# 01-MYB-Y6ULX.net
KiCad netlist of a schematic drawn in Altium Designer
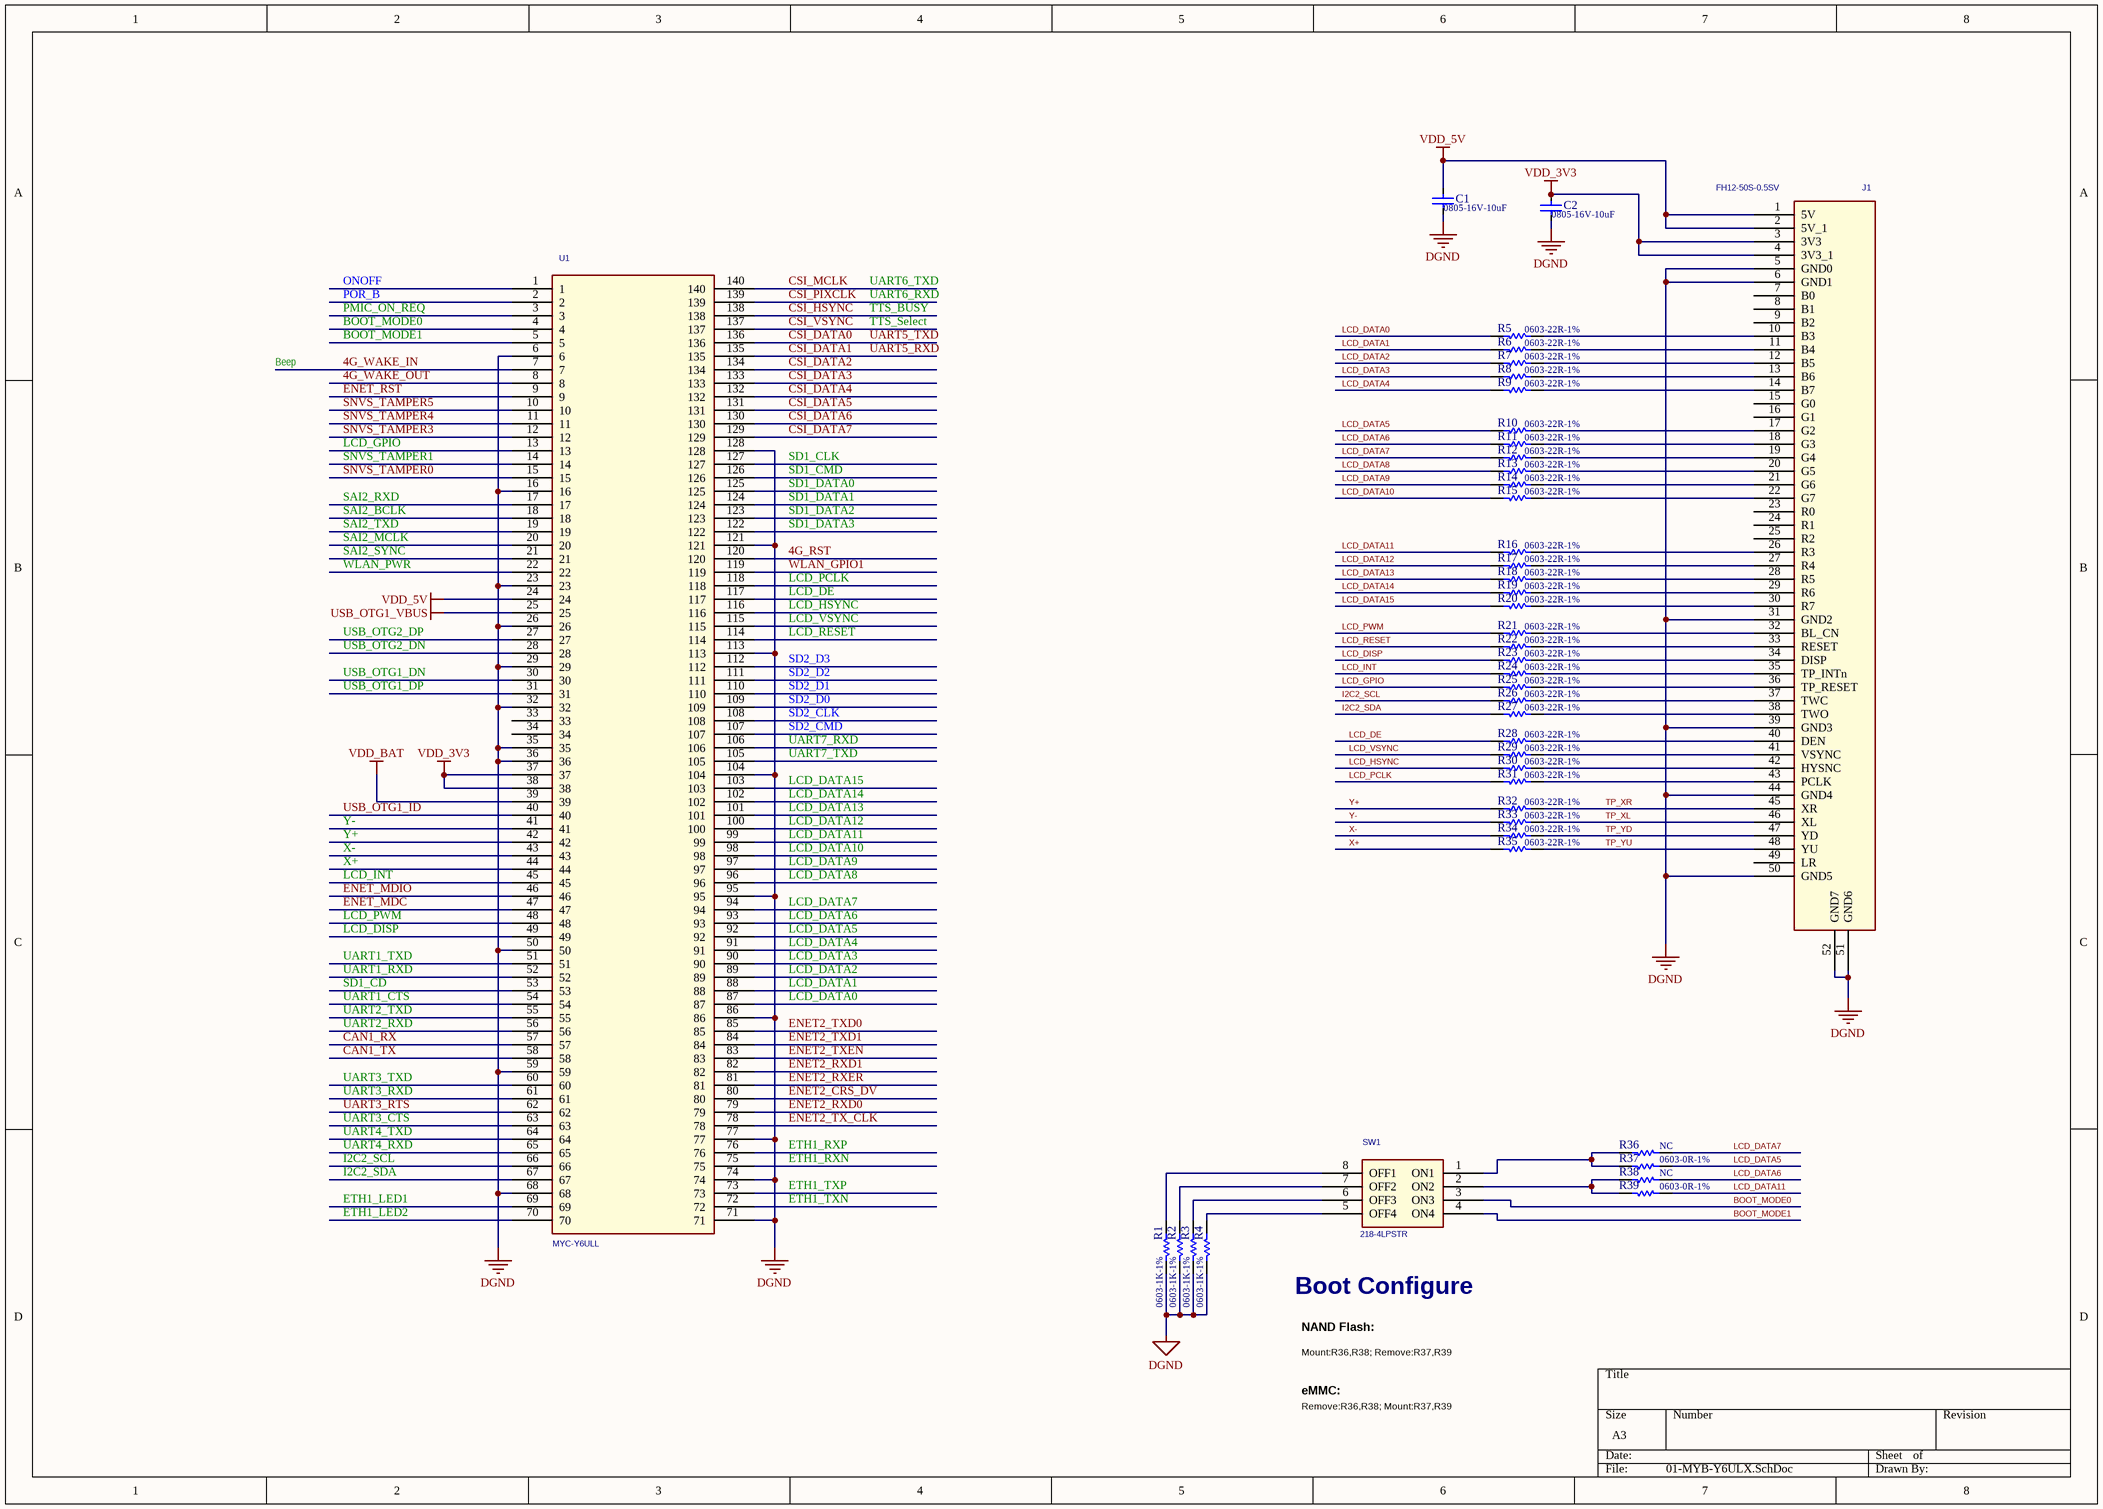
[diagram p0: 01-MYB-Y6ULX.SchDoc]

(export (version "E")
  (design (tool "Eeschema 10.0.6"))
  (components
    (comp (ref "C1")
      (value "0805-16V-10uF")
      (footprint "0805C - 3D")
      (description "Capacitor")
      (fields (field (name "PUBLISHER") "Altium Limited"))
      (libsource (lib "Miscellaneous Devices") (part "Cap"))
    )
    (comp (ref "C2")
      (value "0805-16V-10uF")
      (footprint "0805C - 3D")
      (description "Capacitor")
      (fields (field (name "PUBLISHER") "Altium Limited"))
      (libsource (lib "Miscellaneous Devices") (part "Cap"))
    )
    (comp (ref "J1")
      (value "FH12-50S-0.5SV")
      (footprint "fpc50-1_0-v")
      (description "FPC Connector,Straight,50Pin,0.5mm Pitch  Flip Vertical  Type ,2MM Height,Tin Plated, white,SMD")
      (fields (field (name "MANUFACTURER") "HRS"))
      (libsource (lib "*") (part "FPC50"))
    )
    (comp (ref "R1")
      (value "0603-1K-1%")
      (footprint "0603R")
      (description "Resistor")
      (fields (field (name "PUBLISHER") "Altium Limited"))
      (libsource (lib "Miscellaneous Devices") (part "Res1"))
    )
    (comp (ref "R2")
      (value "0603-1K-1%")
      (footprint "0603R")
      (description "Resistor")
      (fields (field (name "PUBLISHER") "Altium Limited"))
      (libsource (lib "Miscellaneous Devices") (part "Res1"))
    )
    (comp (ref "R3")
      (value "0603-1K-1%")
      (footprint "0603R")
      (description "Resistor")
      (fields (field (name "PUBLISHER") "Altium Limited"))
      (libsource (lib "Miscellaneous Devices") (part "Res1"))
    )
    (comp (ref "R4")
      (value "0603-1K-1%")
      (footprint "0603R")
      (description "Resistor")
      (fields (field (name "PUBLISHER") "Altium Limited"))
      (libsource (lib "Miscellaneous Devices") (part "Res1"))
    )
    (comp (ref "R5")
      (value "0603-22R-1%")
      (footprint "0603R")
      (description "Resistor")
      (fields (field (name "PUBLISHER") "Altium Limited"))
      (libsource (lib "Miscellaneous Devices") (part "Res1"))
    )
    (comp (ref "R6")
      (value "0603-22R-1%")
      (footprint "0603R")
      (description "Resistor")
      (fields (field (name "PUBLISHER") "Altium Limited"))
      (libsource (lib "Miscellaneous Devices") (part "Res1"))
    )
    (comp (ref "R7")
      (value "0603-22R-1%")
      (footprint "0603R")
      (description "Resistor")
      (fields (field (name "PUBLISHER") "Altium Limited"))
      (libsource (lib "Miscellaneous Devices") (part "Res1"))
    )
    (comp (ref "R8")
      (value "0603-22R-1%")
      (footprint "0603R")
      (description "Resistor")
      (fields (field (name "PUBLISHER") "Altium Limited"))
      (libsource (lib "Miscellaneous Devices") (part "Res1"))
    )
    (comp (ref "R9")
      (value "0603-22R-1%")
      (footprint "0603R")
      (description "Resistor")
      (fields (field (name "PUBLISHER") "Altium Limited"))
      (libsource (lib "Miscellaneous Devices") (part "Res1"))
    )
    (comp (ref "R10")
      (value "0603-22R-1%")
      (footprint "0603R")
      (description "Resistor")
      (fields (field (name "PUBLISHER") "Altium Limited"))
      (libsource (lib "Miscellaneous Devices") (part "Res1"))
    )
    (comp (ref "R11")
      (value "0603-22R-1%")
      (footprint "0603R")
      (description "Resistor")
      (fields (field (name "PUBLISHER") "Altium Limited"))
      (libsource (lib "Miscellaneous Devices") (part "Res1"))
    )
    (comp (ref "R12")
      (value "0603-22R-1%")
      (footprint "0603R")
      (description "Resistor")
      (fields (field (name "PUBLISHER") "Altium Limited"))
      (libsource (lib "Miscellaneous Devices") (part "Res1"))
    )
    (comp (ref "R13")
      (value "0603-22R-1%")
      (footprint "0603R")
      (description "Resistor")
      (fields (field (name "PUBLISHER") "Altium Limited"))
      (libsource (lib "Miscellaneous Devices") (part "Res1"))
    )
    (comp (ref "R14")
      (value "0603-22R-1%")
      (footprint "0603R")
      (description "Resistor")
      (fields (field (name "PUBLISHER") "Altium Limited"))
      (libsource (lib "Miscellaneous Devices") (part "Res1"))
    )
    (comp (ref "R15")
      (value "0603-22R-1%")
      (footprint "0603R")
      (description "Resistor")
      (fields (field (name "PUBLISHER") "Altium Limited"))
      (libsource (lib "Miscellaneous Devices") (part "Res1"))
    )
    (comp (ref "R16")
      (value "0603-22R-1%")
      (footprint "0603R")
      (description "Resistor")
      (fields (field (name "PUBLISHER") "Altium Limited"))
      (libsource (lib "Miscellaneous Devices") (part "Res1"))
    )
    (comp (ref "R17")
      (value "0603-22R-1%")
      (footprint "0603R")
      (description "Resistor")
      (fields (field (name "PUBLISHER") "Altium Limited"))
      (libsource (lib "Miscellaneous Devices") (part "Res1"))
    )
    (comp (ref "R18")
      (value "0603-22R-1%")
      (footprint "0603R")
      (description "Resistor")
      (fields (field (name "PUBLISHER") "Altium Limited"))
      (libsource (lib "Miscellaneous Devices") (part "Res1"))
    )
    (comp (ref "R19")
      (value "0603-22R-1%")
      (footprint "0603R")
      (description "Resistor")
      (fields (field (name "PUBLISHER") "Altium Limited"))
      (libsource (lib "Miscellaneous Devices") (part "Res1"))
    )
    (comp (ref "R20")
      (value "0603-22R-1%")
      (footprint "0603R")
      (description "Resistor")
      (fields (field (name "PUBLISHER") "Altium Limited"))
      (libsource (lib "Miscellaneous Devices") (part "Res1"))
    )
    (comp (ref "R21")
      (value "0603-22R-1%")
      (footprint "0603R")
      (description "Resistor")
      (fields (field (name "PUBLISHER") "Altium Limited"))
      (libsource (lib "Miscellaneous Devices") (part "Res1"))
    )
    (comp (ref "R22")
      (value "0603-22R-1%")
      (footprint "0603R")
      (description "Resistor")
      (fields (field (name "PUBLISHER") "Altium Limited"))
      (libsource (lib "Miscellaneous Devices") (part "Res1"))
    )
    (comp (ref "R23")
      (value "0603-22R-1%")
      (footprint "0603R")
      (description "Resistor")
      (fields (field (name "PUBLISHER") "Altium Limited"))
      (libsource (lib "Miscellaneous Devices") (part "Res1"))
    )
    (comp (ref "R24")
      (value "0603-22R-1%")
      (footprint "0603R")
      (description "Resistor")
      (fields (field (name "PUBLISHER") "Altium Limited"))
      (libsource (lib "Miscellaneous Devices") (part "Res1"))
    )
    (comp (ref "R25")
      (value "0603-22R-1%")
      (footprint "0603R")
      (description "Resistor")
      (fields (field (name "PUBLISHER") "Altium Limited"))
      (libsource (lib "Miscellaneous Devices") (part "Res1"))
    )
    (comp (ref "R26")
      (value "0603-22R-1%")
      (footprint "0603R")
      (description "Resistor")
      (fields (field (name "PUBLISHER") "Altium Limited"))
      (libsource (lib "Miscellaneous Devices") (part "Res1"))
    )
    (comp (ref "R27")
      (value "0603-22R-1%")
      (footprint "0603R")
      (description "Resistor")
      (fields (field (name "PUBLISHER") "Altium Limited"))
      (libsource (lib "Miscellaneous Devices") (part "Res1"))
    )
    (comp (ref "R28")
      (value "0603-22R-1%")
      (footprint "0603R")
      (description "Resistor")
      (fields (field (name "PUBLISHER") "Altium Limited"))
      (libsource (lib "Miscellaneous Devices") (part "Res1"))
    )
    (comp (ref "R29")
      (value "0603-22R-1%")
      (footprint "0603R")
      (description "Resistor")
      (fields (field (name "PUBLISHER") "Altium Limited"))
      (libsource (lib "Miscellaneous Devices") (part "Res1"))
    )
    (comp (ref "R30")
      (value "0603-22R-1%")
      (footprint "0603R")
      (description "Resistor")
      (fields (field (name "PUBLISHER") "Altium Limited"))
      (libsource (lib "Miscellaneous Devices") (part "Res1"))
    )
    (comp (ref "R31")
      (value "0603-22R-1%")
      (footprint "0603R")
      (description "Resistor")
      (fields (field (name "PUBLISHER") "Altium Limited"))
      (libsource (lib "Miscellaneous Devices") (part "Res1"))
    )
    (comp (ref "R32")
      (value "0603-22R-1%")
      (footprint "0603R")
      (description "Resistor")
      (fields (field (name "PUBLISHER") "Altium Limited"))
      (libsource (lib "Miscellaneous Devices") (part "Res1"))
    )
    (comp (ref "R33")
      (value "0603-22R-1%")
      (footprint "0603R")
      (description "Resistor")
      (fields (field (name "PUBLISHER") "Altium Limited"))
      (libsource (lib "Miscellaneous Devices") (part "Res1"))
    )
    (comp (ref "R34")
      (value "0603-22R-1%")
      (footprint "0603R")
      (description "Resistor")
      (fields (field (name "PUBLISHER") "Altium Limited"))
      (libsource (lib "Miscellaneous Devices") (part "Res1"))
    )
    (comp (ref "R35")
      (value "0603-22R-1%")
      (footprint "0603R")
      (description "Resistor")
      (fields (field (name "PUBLISHER") "Altium Limited"))
      (libsource (lib "Miscellaneous Devices") (part "Res1"))
    )
    (comp (ref "R36")
      (value "NC")
      (footprint "0603R")
      (description "Resistor")
      (fields (field (name "PUBLISHER") "Altium Limited"))
      (libsource (lib "Miscellaneous Devices") (part "Res1"))
    )
    (comp (ref "R37")
      (value "0603-0R-1%")
      (footprint "0603R")
      (description "Resistor")
      (fields (field (name "PUBLISHER") "Altium Limited"))
      (libsource (lib "Miscellaneous Devices") (part "Res1"))
    )
    (comp (ref "R38")
      (value "NC")
      (footprint "0603R")
      (description "Resistor")
      (fields (field (name "PUBLISHER") "Altium Limited"))
      (libsource (lib "Miscellaneous Devices") (part "Res1"))
    )
    (comp (ref "R39")
      (value "0603-0R-1%")
      (footprint "0603R")
      (description "Resistor")
      (fields (field (name "PUBLISHER") "Altium Limited"))
      (libsource (lib "Miscellaneous Devices") (part "Res1"))
    )
    (comp (ref "SW1")
      (value "218-4LPSTR")
      (footprint "sw-1x4")
      (fields (field (name "MANUFACTURER") "CTS"))
      (libsource (lib "*") (part "SWITCH-4"))
    )
    (comp (ref "U1")
      (value "MYC-Y6ULL")
      (footprint "YOUPK37X39_1_00-SMD")
      (libsource (lib "*") (part "AM335X_QFN_2"))
    )
  )
  (nets
    (net (code "1") (name "/4G_RST") (class "Default")
      (node (ref "U1") (pin "120") (pinfunction "120_120") (pintype "passive"))
    )
    (net (code "2") (name "/4G_WAKE_IN") (class "Default")
      (node (ref "U1") (pin "7") (pinfunction "7_7") (pintype "passive"))
    )
    (net (code "3") (name "/4G_WAKE_OUT") (class "Default")
      (node (ref "U1") (pin "8") (pinfunction "8_8") (pintype "passive"))
    )
    (net (code "4") (name "/BOOT_MODE0") (class "Default")
      (node (ref "SW1") (pin "3") (pinfunction "ON3_3") (pintype "passive"))
      (node (ref "U1") (pin "4") (pinfunction "4_4") (pintype "passive"))
    )
    (net (code "5") (name "/BOOT_MODE1") (class "Default")
      (node (ref "SW1") (pin "4") (pinfunction "ON4_4") (pintype "passive"))
      (node (ref "U1") (pin "5") (pinfunction "5_5") (pintype "passive"))
    )
    (net (code "6") (name "/CAN1_RX") (class "Default")
      (node (ref "U1") (pin "57") (pinfunction "57_57") (pintype "passive"))
    )
    (net (code "7") (name "/CAN1_TX") (class "Default")
      (node (ref "U1") (pin "58") (pinfunction "58_58") (pintype "passive"))
    )
    (net (code "8") (name "/CSI_DATA0") (class "Default")
      (node (ref "U1") (pin "136") (pinfunction "136_136") (pintype "passive"))
    )
    (net (code "9") (name "/CSI_DATA1") (class "Default")
      (node (ref "U1") (pin "135") (pinfunction "135_135") (pintype "passive"))
    )
    (net (code "10") (name "/CSI_DATA2") (class "Default")
      (node (ref "U1") (pin "134") (pinfunction "134_134") (pintype "passive"))
    )
    (net (code "11") (name "/CSI_DATA3") (class "Default")
      (node (ref "U1") (pin "133") (pinfunction "133_133") (pintype "passive"))
    )
    (net (code "12") (name "/CSI_DATA4") (class "Default")
      (node (ref "U1") (pin "132") (pinfunction "132_132") (pintype "passive"))
    )
    (net (code "13") (name "/CSI_DATA5") (class "Default")
      (node (ref "U1") (pin "131") (pinfunction "131_131") (pintype "passive"))
    )
    (net (code "14") (name "/CSI_DATA6") (class "Default")
      (node (ref "U1") (pin "130") (pinfunction "130_130") (pintype "passive"))
    )
    (net (code "15") (name "/CSI_DATA7") (class "Default")
      (node (ref "U1") (pin "129") (pinfunction "129_129") (pintype "passive"))
    )
    (net (code "16") (name "/CSI_HSYNC") (class "Default")
      (node (ref "U1") (pin "138") (pinfunction "138_138") (pintype "passive"))
    )
    (net (code "17") (name "/CSI_MCLK") (class "Default")
      (node (ref "U1") (pin "140") (pinfunction "140_140") (pintype "passive"))
    )
    (net (code "18") (name "/CSI_PIXCLK") (class "Default")
      (node (ref "U1") (pin "139") (pinfunction "139_139") (pintype "passive"))
    )
    (net (code "19") (name "/CSI_VSYNC") (class "Default")
      (node (ref "U1") (pin "137") (pinfunction "137_137") (pintype "passive"))
    )
    (net (code "20") (name "/ENET2_CRS_DV") (class "Default")
      (node (ref "U1") (pin "80") (pinfunction "80_80") (pintype "passive"))
    )
    (net (code "21") (name "/ENET2_RXD0") (class "Default")
      (node (ref "U1") (pin "79") (pinfunction "79_79") (pintype "passive"))
    )
    (net (code "22") (name "/ENET2_RXD1") (class "Default")
      (node (ref "U1") (pin "82") (pinfunction "82_82") (pintype "passive"))
    )
    (net (code "23") (name "/ENET2_RXER") (class "Default")
      (node (ref "U1") (pin "81") (pinfunction "81_81") (pintype "passive"))
    )
    (net (code "24") (name "/ENET2_TXD0") (class "Default")
      (node (ref "U1") (pin "85") (pinfunction "85_85") (pintype "passive"))
    )
    (net (code "25") (name "/ENET2_TXD1") (class "Default")
      (node (ref "U1") (pin "84") (pinfunction "84_84") (pintype "passive"))
    )
    (net (code "26") (name "/ENET2_TXEN") (class "Default")
      (node (ref "U1") (pin "83") (pinfunction "83_83") (pintype "passive"))
    )
    (net (code "27") (name "/ENET2_TX_CLK") (class "Default")
      (node (ref "U1") (pin "78") (pinfunction "78_78") (pintype "passive"))
    )
    (net (code "28") (name "/ENET_MDC") (class "Default")
      (node (ref "U1") (pin "47") (pinfunction "47_47") (pintype "passive"))
    )
    (net (code "29") (name "/ENET_MDIO") (class "Default")
      (node (ref "U1") (pin "46") (pinfunction "46_46") (pintype "passive"))
    )
    (net (code "30") (name "/ENET_RST") (class "Default")
      (node (ref "U1") (pin "9") (pinfunction "9_9") (pintype "passive"))
    )
    (net (code "31") (name "/ETH1_LED1") (class "Default")
      (node (ref "U1") (pin "69") (pinfunction "69_69") (pintype "passive"))
    )
    (net (code "32") (name "/ETH1_LED2") (class "Default")
      (node (ref "U1") (pin "70") (pinfunction "70_70") (pintype "passive"))
    )
    (net (code "33") (name "/ETH1_RXN") (class "Default")
      (node (ref "U1") (pin "75") (pinfunction "75_75") (pintype "passive"))
    )
    (net (code "34") (name "/ETH1_RXP") (class "Default")
      (node (ref "U1") (pin "76") (pinfunction "76_76") (pintype "passive"))
    )
    (net (code "35") (name "/ETH1_TXN") (class "Default")
      (node (ref "U1") (pin "72") (pinfunction "72_72") (pintype "passive"))
    )
    (net (code "36") (name "/ETH1_TXP") (class "Default")
      (node (ref "U1") (pin "73") (pinfunction "73_73") (pintype "passive"))
    )
    (net (code "37") (name "/I2C2_SCL") (class "Default")
      (node (ref "R26") (pin "1") (pinfunction "1_1") (pintype "passive"))
      (node (ref "U1") (pin "66") (pinfunction "66_66") (pintype "passive"))
    )
    (net (code "38") (name "/I2C2_SDA") (class "Default")
      (node (ref "R27") (pin "1") (pinfunction "1_1") (pintype "passive"))
      (node (ref "U1") (pin "67") (pinfunction "67_67") (pintype "passive"))
    )
    (net (code "39") (name "/LCD_DATA0") (class "Default")
      (node (ref "R5") (pin "1") (pinfunction "1_1") (pintype "passive"))
      (node (ref "U1") (pin "87") (pinfunction "87_87") (pintype "passive"))
    )
    (net (code "40") (name "/LCD_DATA1") (class "Default")
      (node (ref "R6") (pin "1") (pinfunction "1_1") (pintype "passive"))
      (node (ref "U1") (pin "88") (pinfunction "88_88") (pintype "passive"))
    )
    (net (code "41") (name "/LCD_DATA2") (class "Default")
      (node (ref "R7") (pin "1") (pinfunction "1_1") (pintype "passive"))
      (node (ref "U1") (pin "89") (pinfunction "89_89") (pintype "passive"))
    )
    (net (code "42") (name "/LCD_DATA3") (class "Default")
      (node (ref "R8") (pin "1") (pinfunction "1_1") (pintype "passive"))
      (node (ref "U1") (pin "90") (pinfunction "90_90") (pintype "passive"))
    )
    (net (code "43") (name "/LCD_DATA4") (class "Default")
      (node (ref "R9") (pin "1") (pinfunction "1_1") (pintype "passive"))
      (node (ref "U1") (pin "91") (pinfunction "91_91") (pintype "passive"))
    )
    (net (code "44") (name "/LCD_DATA5") (class "Default")
      (node (ref "R10") (pin "1") (pinfunction "1_1") (pintype "passive"))
      (node (ref "R37") (pin "2") (pinfunction "2_2") (pintype "passive"))
      (node (ref "U1") (pin "92") (pinfunction "92_92") (pintype "passive"))
    )
    (net (code "45") (name "/LCD_DATA6") (class "Default")
      (node (ref "R11") (pin "1") (pinfunction "1_1") (pintype "passive"))
      (node (ref "R38") (pin "2") (pinfunction "2_2") (pintype "passive"))
      (node (ref "U1") (pin "93") (pinfunction "93_93") (pintype "passive"))
    )
    (net (code "46") (name "/LCD_DATA7") (class "Default")
      (node (ref "R12") (pin "1") (pinfunction "1_1") (pintype "passive"))
      (node (ref "R36") (pin "2") (pinfunction "2_2") (pintype "passive"))
      (node (ref "U1") (pin "94") (pinfunction "94_94") (pintype "passive"))
    )
    (net (code "47") (name "/LCD_DATA8") (class "Default")
      (node (ref "R13") (pin "1") (pinfunction "1_1") (pintype "passive"))
      (node (ref "U1") (pin "96") (pinfunction "96_96") (pintype "passive"))
    )
    (net (code "48") (name "/LCD_DATA9") (class "Default")
      (node (ref "R14") (pin "1") (pinfunction "1_1") (pintype "passive"))
      (node (ref "U1") (pin "97") (pinfunction "97_97") (pintype "passive"))
    )
    (net (code "49") (name "/LCD_DATA10") (class "Default")
      (node (ref "R15") (pin "1") (pinfunction "1_1") (pintype "passive"))
      (node (ref "U1") (pin "98") (pinfunction "98_98") (pintype "passive"))
    )
    (net (code "50") (name "/LCD_DATA11") (class "Default")
      (node (ref "R16") (pin "1") (pinfunction "1_1") (pintype "passive"))
      (node (ref "R39") (pin "2") (pinfunction "2_2") (pintype "passive"))
      (node (ref "U1") (pin "99") (pinfunction "99_99") (pintype "passive"))
    )
    (net (code "51") (name "/LCD_DATA12") (class "Default")
      (node (ref "R17") (pin "1") (pinfunction "1_1") (pintype "passive"))
      (node (ref "U1") (pin "100") (pinfunction "100_100") (pintype "passive"))
    )
    (net (code "52") (name "/LCD_DATA13") (class "Default")
      (node (ref "R18") (pin "1") (pinfunction "1_1") (pintype "passive"))
      (node (ref "U1") (pin "101") (pinfunction "101_101") (pintype "passive"))
    )
    (net (code "53") (name "/LCD_DATA14") (class "Default")
      (node (ref "R19") (pin "1") (pinfunction "1_1") (pintype "passive"))
      (node (ref "U1") (pin "102") (pinfunction "102_102") (pintype "passive"))
    )
    (net (code "54") (name "/LCD_DATA15") (class "Default")
      (node (ref "R20") (pin "1") (pinfunction "1_1") (pintype "passive"))
      (node (ref "U1") (pin "103") (pinfunction "103_103") (pintype "passive"))
    )
    (net (code "55") (name "/LCD_DE") (class "Default")
      (node (ref "R28") (pin "1") (pinfunction "1_1") (pintype "passive"))
      (node (ref "U1") (pin "117") (pinfunction "117_117") (pintype "passive"))
    )
    (net (code "56") (name "/LCD_DISP") (class "Default")
      (node (ref "R23") (pin "1") (pinfunction "1_1") (pintype "passive"))
      (node (ref "U1") (pin "49") (pinfunction "49_49") (pintype "passive"))
    )
    (net (code "57") (name "/LCD_GPIO") (class "Default")
      (node (ref "R25") (pin "1") (pinfunction "1_1") (pintype "passive"))
      (node (ref "U1") (pin "13") (pinfunction "13_13") (pintype "passive"))
    )
    (net (code "58") (name "/LCD_HSYNC") (class "Default")
      (node (ref "R30") (pin "1") (pinfunction "1_1") (pintype "passive"))
      (node (ref "U1") (pin "116") (pinfunction "116_116") (pintype "passive"))
    )
    (net (code "59") (name "/LCD_INT") (class "Default")
      (node (ref "R24") (pin "1") (pinfunction "1_1") (pintype "passive"))
      (node (ref "U1") (pin "45") (pinfunction "45_45") (pintype "passive"))
    )
    (net (code "60") (name "/LCD_PCLK") (class "Default")
      (node (ref "R31") (pin "1") (pinfunction "1_1") (pintype "passive"))
      (node (ref "U1") (pin "118") (pinfunction "118_118") (pintype "passive"))
    )
    (net (code "61") (name "/LCD_PWM") (class "Default")
      (node (ref "R21") (pin "1") (pinfunction "1_1") (pintype "passive"))
      (node (ref "U1") (pin "48") (pinfunction "48_48") (pintype "passive"))
    )
    (net (code "62") (name "/LCD_RESET") (class "Default")
      (node (ref "R22") (pin "1") (pinfunction "1_1") (pintype "passive"))
      (node (ref "U1") (pin "114") (pinfunction "114_114") (pintype "passive"))
    )
    (net (code "63") (name "/LCD_VSYNC") (class "Default")
      (node (ref "R29") (pin "1") (pinfunction "1_1") (pintype "passive"))
      (node (ref "U1") (pin "115") (pinfunction "115_115") (pintype "passive"))
    )
    (net (code "64") (name "/ONOFF") (class "Default")
      (node (ref "U1") (pin "1") (pinfunction "1_1") (pintype "passive"))
    )
    (net (code "65") (name "/PMIC_ON_REQ") (class "Default")
      (node (ref "U1") (pin "3") (pinfunction "3_3") (pintype "passive"))
    )
    (net (code "66") (name "/POR_B") (class "Default")
      (node (ref "U1") (pin "2") (pinfunction "2_2") (pintype "passive"))
    )
    (net (code "67") (name "/SAI2_BCLK") (class "Default")
      (node (ref "U1") (pin "18") (pinfunction "18_18") (pintype "passive"))
    )
    (net (code "68") (name "/SAI2_MCLK") (class "Default")
      (node (ref "U1") (pin "20") (pinfunction "20_20") (pintype "passive"))
    )
    (net (code "69") (name "/SAI2_RXD") (class "Default")
      (node (ref "U1") (pin "17") (pinfunction "17_17") (pintype "passive"))
    )
    (net (code "70") (name "/SAI2_SYNC") (class "Default")
      (node (ref "U1") (pin "21") (pinfunction "21_21") (pintype "passive"))
    )
    (net (code "71") (name "/SAI2_TXD") (class "Default")
      (node (ref "U1") (pin "19") (pinfunction "19_19") (pintype "passive"))
    )
    (net (code "72") (name "/SD1_CD") (class "Default")
      (node (ref "U1") (pin "53") (pinfunction "53_53") (pintype "passive"))
    )
    (net (code "73") (name "/SD1_CLK") (class "Default")
      (node (ref "U1") (pin "127") (pinfunction "127_127") (pintype "passive"))
    )
    (net (code "74") (name "/SD1_CMD") (class "Default")
      (node (ref "U1") (pin "126") (pinfunction "126_126") (pintype "passive"))
    )
    (net (code "75") (name "/SD1_DATA0") (class "Default")
      (node (ref "U1") (pin "125") (pinfunction "125_125") (pintype "passive"))
    )
    (net (code "76") (name "/SD1_DATA1") (class "Default")
      (node (ref "U1") (pin "124") (pinfunction "124_124") (pintype "passive"))
    )
    (net (code "77") (name "/SD1_DATA2") (class "Default")
      (node (ref "U1") (pin "123") (pinfunction "123_123") (pintype "passive"))
    )
    (net (code "78") (name "/SD1_DATA3") (class "Default")
      (node (ref "U1") (pin "122") (pinfunction "122_122") (pintype "passive"))
    )
    (net (code "79") (name "/SD2_CLK") (class "Default")
      (node (ref "U1") (pin "108") (pinfunction "108_108") (pintype "passive"))
    )
    (net (code "80") (name "/SD2_CMD") (class "Default")
      (node (ref "U1") (pin "107") (pinfunction "107_107") (pintype "passive"))
    )
    (net (code "81") (name "/SD2_D0") (class "Default")
      (node (ref "U1") (pin "109") (pinfunction "109_109") (pintype "passive"))
    )
    (net (code "82") (name "/SD2_D1") (class "Default")
      (node (ref "U1") (pin "110") (pinfunction "110_110") (pintype "passive"))
    )
    (net (code "83") (name "/SD2_D2") (class "Default")
      (node (ref "U1") (pin "111") (pinfunction "111_111") (pintype "passive"))
    )
    (net (code "84") (name "/SD2_D3") (class "Default")
      (node (ref "U1") (pin "112") (pinfunction "112_112") (pintype "passive"))
    )
    (net (code "85") (name "/SNVS_TAMPER0") (class "Default")
      (node (ref "U1") (pin "15") (pinfunction "15_15") (pintype "passive"))
    )
    (net (code "86") (name "/SNVS_TAMPER1") (class "Default")
      (node (ref "U1") (pin "14") (pinfunction "14_14") (pintype "passive"))
    )
    (net (code "87") (name "/SNVS_TAMPER3") (class "Default")
      (node (ref "U1") (pin "12") (pinfunction "12_12") (pintype "passive"))
    )
    (net (code "88") (name "/SNVS_TAMPER4") (class "Default")
      (node (ref "U1") (pin "11") (pinfunction "11_11") (pintype "passive"))
    )
    (net (code "89") (name "/SNVS_TAMPER5") (class "Default")
      (node (ref "U1") (pin "10") (pinfunction "10_10") (pintype "passive"))
    )
    (net (code "90") (name "/TP_XL") (class "Default")
      (node (ref "J1") (pin "46") (pinfunction "XL_46") (pintype "passive"))
      (node (ref "R33") (pin "2") (pinfunction "2_2") (pintype "passive"))
    )
    (net (code "91") (name "/TP_XR") (class "Default")
      (node (ref "J1") (pin "45") (pinfunction "XR_45") (pintype "passive"))
      (node (ref "R32") (pin "2") (pinfunction "2_2") (pintype "passive"))
    )
    (net (code "92") (name "/TP_YD") (class "Default")
      (node (ref "J1") (pin "47") (pinfunction "YD_47") (pintype "passive"))
      (node (ref "R34") (pin "2") (pinfunction "2_2") (pintype "passive"))
    )
    (net (code "93") (name "/TP_YU") (class "Default")
      (node (ref "J1") (pin "48") (pinfunction "YU_48") (pintype "passive"))
      (node (ref "R35") (pin "2") (pinfunction "2_2") (pintype "passive"))
    )
    (net (code "94") (name "/UART1_CTS") (class "Default")
      (node (ref "U1") (pin "54") (pinfunction "54_54") (pintype "passive"))
    )
    (net (code "95") (name "/UART1_RXD") (class "Default")
      (node (ref "U1") (pin "52") (pinfunction "52_52") (pintype "passive"))
    )
    (net (code "96") (name "/UART1_TXD") (class "Default")
      (node (ref "U1") (pin "51") (pinfunction "51_51") (pintype "passive"))
    )
    (net (code "97") (name "/UART2_RXD") (class "Default")
      (node (ref "U1") (pin "56") (pinfunction "56_56") (pintype "passive"))
    )
    (net (code "98") (name "/UART2_TXD") (class "Default")
      (node (ref "U1") (pin "55") (pinfunction "55_55") (pintype "passive"))
    )
    (net (code "99") (name "/UART3_CTS") (class "Default")
      (node (ref "U1") (pin "63") (pinfunction "63_63") (pintype "passive"))
    )
    (net (code "100") (name "/UART3_RTS") (class "Default")
      (node (ref "U1") (pin "62") (pinfunction "62_62") (pintype "passive"))
    )
    (net (code "101") (name "/UART3_RXD") (class "Default")
      (node (ref "U1") (pin "61") (pinfunction "61_61") (pintype "passive"))
    )
    (net (code "102") (name "/UART3_TXD") (class "Default")
      (node (ref "U1") (pin "60") (pinfunction "60_60") (pintype "passive"))
    )
    (net (code "103") (name "/UART4_RXD") (class "Default")
      (node (ref "U1") (pin "65") (pinfunction "65_65") (pintype "passive"))
    )
    (net (code "104") (name "/UART4_TXD") (class "Default")
      (node (ref "U1") (pin "64") (pinfunction "64_64") (pintype "passive"))
    )
    (net (code "105") (name "/UART7_RXD") (class "Default")
      (node (ref "U1") (pin "106") (pinfunction "106_106") (pintype "passive"))
    )
    (net (code "106") (name "/UART7_TXD") (class "Default")
      (node (ref "U1") (pin "105") (pinfunction "105_105") (pintype "passive"))
    )
    (net (code "107") (name "/USB_OTG1_DN") (class "Default")
      (node (ref "U1") (pin "30") (pinfunction "30_30") (pintype "passive"))
    )
    (net (code "108") (name "/USB_OTG1_DP") (class "Default")
      (node (ref "U1") (pin "31") (pinfunction "31_31") (pintype "passive"))
    )
    (net (code "109") (name "/USB_OTG1_ID") (class "Default")
      (node (ref "U1") (pin "40") (pinfunction "40_40") (pintype "passive"))
    )
    (net (code "110") (name "/USB_OTG2_DN") (class "Default")
      (node (ref "U1") (pin "28") (pinfunction "28_28") (pintype "passive"))
    )
    (net (code "111") (name "/USB_OTG2_DP") (class "Default")
      (node (ref "U1") (pin "27") (pinfunction "27_27") (pintype "passive"))
    )
    (net (code "112") (name "/WLAN_GPIO1") (class "Default")
      (node (ref "U1") (pin "119") (pinfunction "119_119") (pintype "passive"))
    )
    (net (code "113") (name "/WLAN_PWR") (class "Default")
      (node (ref "U1") (pin "22") (pinfunction "22_22") (pintype "passive"))
    )
    (net (code "114") (name "/X+") (class "Default")
      (node (ref "R35") (pin "1") (pinfunction "1_1") (pintype "passive"))
      (node (ref "U1") (pin "44") (pinfunction "44_44") (pintype "passive"))
    )
    (net (code "115") (name "/X-") (class "Default")
      (node (ref "R34") (pin "1") (pinfunction "1_1") (pintype "passive"))
      (node (ref "U1") (pin "43") (pinfunction "43_43") (pintype "passive"))
    )
    (net (code "116") (name "/Y+") (class "Default")
      (node (ref "R32") (pin "1") (pinfunction "1_1") (pintype "passive"))
      (node (ref "U1") (pin "42") (pinfunction "42_42") (pintype "passive"))
    )
    (net (code "117") (name "/Y-") (class "Default")
      (node (ref "R33") (pin "1") (pinfunction "1_1") (pintype "passive"))
      (node (ref "U1") (pin "41") (pinfunction "41_41") (pintype "passive"))
    )
    (net (code "118") (name "DGND") (class "Default")
      (node (ref "C1") (pin "2") (pinfunction "2_2") (pintype "passive"))
      (node (ref "C2") (pin "2") (pinfunction "2_2") (pintype "passive"))
      (node (ref "J1") (pin "31") (pinfunction "GND2_31") (pintype "passive"))
      (node (ref "J1") (pin "39") (pinfunction "GND3_39") (pintype "passive"))
      (node (ref "J1") (pin "44") (pinfunction "GND4_44") (pintype "passive"))
      (node (ref "J1") (pin "5") (pinfunction "GND0_5") (pintype "passive"))
      (node (ref "J1") (pin "50") (pinfunction "GND5_50") (pintype "passive"))
      (node (ref "J1") (pin "51") (pinfunction "GND6_51") (pintype "passive"))
      (node (ref "J1") (pin "52") (pinfunction "GND7_52") (pintype "passive"))
      (node (ref "J1") (pin "6") (pinfunction "GND1_6") (pintype "passive"))
      (node (ref "R1") (pin "1") (pinfunction "1_1") (pintype "passive"))
      (node (ref "R2") (pin "1") (pinfunction "1_1") (pintype "passive"))
      (node (ref "R3") (pin "1") (pinfunction "1_1") (pintype "passive"))
      (node (ref "R4") (pin "1") (pinfunction "1_1") (pintype "passive"))
      (node (ref "U1") (pin "104") (pinfunction "104_104") (pintype "passive"))
      (node (ref "U1") (pin "113") (pinfunction "113_113") (pintype "passive"))
      (node (ref "U1") (pin "121") (pinfunction "121_121") (pintype "passive"))
      (node (ref "U1") (pin "128") (pinfunction "128_128") (pintype "passive"))
      (node (ref "U1") (pin "16") (pinfunction "16_16") (pintype "passive"))
      (node (ref "U1") (pin "23") (pinfunction "23_23") (pintype "passive"))
      (node (ref "U1") (pin "26") (pinfunction "26_26") (pintype "passive"))
      (node (ref "U1") (pin "29") (pinfunction "29_29") (pintype "passive"))
      (node (ref "U1") (pin "32") (pinfunction "32_32") (pintype "passive"))
      (node (ref "U1") (pin "35") (pinfunction "35_35") (pintype "passive"))
      (node (ref "U1") (pin "36") (pinfunction "36_36") (pintype "passive"))
      (node (ref "U1") (pin "50") (pinfunction "50_50") (pintype "passive"))
      (node (ref "U1") (pin "59") (pinfunction "59_59") (pintype "passive"))
      (node (ref "U1") (pin "6") (pinfunction "6_6") (pintype "passive"))
      (node (ref "U1") (pin "68") (pinfunction "68_68") (pintype "passive"))
      (node (ref "U1") (pin "71") (pinfunction "71_71") (pintype "passive"))
      (node (ref "U1") (pin "74") (pinfunction "74_74") (pintype "passive"))
      (node (ref "U1") (pin "77") (pinfunction "77_77") (pintype "passive"))
      (node (ref "U1") (pin "86") (pinfunction "86_86") (pintype "passive"))
      (node (ref "U1") (pin "95") (pinfunction "95_95") (pintype "passive"))
    )
    (net (code "119") (name "Net-(J1-B3)") (class "Default")
      (node (ref "J1") (pin "10") (pinfunction "B3_10") (pintype "passive"))
      (node (ref "R5") (pin "2") (pinfunction "2_2") (pintype "passive"))
    )
    (net (code "120") (name "Net-(J1-B4)") (class "Default")
      (node (ref "J1") (pin "11") (pinfunction "B4_11") (pintype "passive"))
      (node (ref "R6") (pin "2") (pinfunction "2_2") (pintype "passive"))
    )
    (net (code "121") (name "Net-(J1-B5)") (class "Default")
      (node (ref "J1") (pin "12") (pinfunction "B5_12") (pintype "passive"))
      (node (ref "R7") (pin "2") (pinfunction "2_2") (pintype "passive"))
    )
    (net (code "122") (name "Net-(J1-B6)") (class "Default")
      (node (ref "J1") (pin "13") (pinfunction "B6_13") (pintype "passive"))
      (node (ref "R8") (pin "2") (pinfunction "2_2") (pintype "passive"))
    )
    (net (code "123") (name "Net-(J1-B7)") (class "Default")
      (node (ref "J1") (pin "14") (pinfunction "B7_14") (pintype "passive"))
      (node (ref "R9") (pin "2") (pinfunction "2_2") (pintype "passive"))
    )
    (net (code "124") (name "Net-(J1-BL_CN)") (class "Default")
      (node (ref "J1") (pin "32") (pinfunction "BL_CN_32") (pintype "passive"))
      (node (ref "R21") (pin "2") (pinfunction "2_2") (pintype "passive"))
    )
    (net (code "125") (name "Net-(J1-DEN)") (class "Default")
      (node (ref "J1") (pin "40") (pinfunction "DEN_40") (pintype "passive"))
      (node (ref "R28") (pin "2") (pinfunction "2_2") (pintype "passive"))
    )
    (net (code "126") (name "Net-(J1-DISP)") (class "Default")
      (node (ref "J1") (pin "34") (pinfunction "DISP_34") (pintype "passive"))
      (node (ref "R23") (pin "2") (pinfunction "2_2") (pintype "passive"))
    )
    (net (code "127") (name "Net-(J1-G2)") (class "Default")
      (node (ref "J1") (pin "17") (pinfunction "G2_17") (pintype "passive"))
      (node (ref "R10") (pin "2") (pinfunction "2_2") (pintype "passive"))
    )
    (net (code "128") (name "Net-(J1-G3)") (class "Default")
      (node (ref "J1") (pin "18") (pinfunction "G3_18") (pintype "passive"))
      (node (ref "R11") (pin "2") (pinfunction "2_2") (pintype "passive"))
    )
    (net (code "129") (name "Net-(J1-G4)") (class "Default")
      (node (ref "J1") (pin "19") (pinfunction "G4_19") (pintype "passive"))
      (node (ref "R12") (pin "2") (pinfunction "2_2") (pintype "passive"))
    )
    (net (code "130") (name "Net-(J1-G5)") (class "Default")
      (node (ref "J1") (pin "20") (pinfunction "G5_20") (pintype "passive"))
      (node (ref "R13") (pin "2") (pinfunction "2_2") (pintype "passive"))
    )
    (net (code "131") (name "Net-(J1-G6)") (class "Default")
      (node (ref "J1") (pin "21") (pinfunction "G6_21") (pintype "passive"))
      (node (ref "R14") (pin "2") (pinfunction "2_2") (pintype "passive"))
    )
    (net (code "132") (name "Net-(J1-G7)") (class "Default")
      (node (ref "J1") (pin "22") (pinfunction "G7_22") (pintype "passive"))
      (node (ref "R15") (pin "2") (pinfunction "2_2") (pintype "passive"))
    )
    (net (code "133") (name "Net-(J1-HYSNC)") (class "Default")
      (node (ref "J1") (pin "42") (pinfunction "HYSNC_42") (pintype "passive"))
      (node (ref "R30") (pin "2") (pinfunction "2_2") (pintype "passive"))
    )
    (net (code "134") (name "Net-(J1-PCLK)") (class "Default")
      (node (ref "J1") (pin "43") (pinfunction "PCLK_43") (pintype "passive"))
      (node (ref "R31") (pin "2") (pinfunction "2_2") (pintype "passive"))
    )
    (net (code "135") (name "Net-(J1-R3)") (class "Default")
      (node (ref "J1") (pin "26") (pinfunction "R3_26") (pintype "passive"))
      (node (ref "R16") (pin "2") (pinfunction "2_2") (pintype "passive"))
    )
    (net (code "136") (name "Net-(J1-R4)") (class "Default")
      (node (ref "J1") (pin "27") (pinfunction "R4_27") (pintype "passive"))
      (node (ref "R17") (pin "2") (pinfunction "2_2") (pintype "passive"))
    )
    (net (code "137") (name "Net-(J1-R5)") (class "Default")
      (node (ref "J1") (pin "28") (pinfunction "R5_28") (pintype "passive"))
      (node (ref "R18") (pin "2") (pinfunction "2_2") (pintype "passive"))
    )
    (net (code "138") (name "Net-(J1-R6)") (class "Default")
      (node (ref "J1") (pin "29") (pinfunction "R6_29") (pintype "passive"))
      (node (ref "R19") (pin "2") (pinfunction "2_2") (pintype "passive"))
    )
    (net (code "139") (name "Net-(J1-R7)") (class "Default")
      (node (ref "J1") (pin "30") (pinfunction "R7_30") (pintype "passive"))
      (node (ref "R20") (pin "2") (pinfunction "2_2") (pintype "passive"))
    )
    (net (code "140") (name "Net-(J1-RESET)") (class "Default")
      (node (ref "J1") (pin "33") (pinfunction "RESET_33") (pintype "passive"))
      (node (ref "R22") (pin "2") (pinfunction "2_2") (pintype "passive"))
    )
    (net (code "141") (name "Net-(J1-TP_INTn)") (class "Default")
      (node (ref "J1") (pin "35") (pinfunction "TP_INTn_35") (pintype "passive"))
      (node (ref "R24") (pin "2") (pinfunction "2_2") (pintype "passive"))
    )
    (net (code "142") (name "Net-(J1-TP_RESET)") (class "Default")
      (node (ref "J1") (pin "36") (pinfunction "TP_RESET_36") (pintype "passive"))
      (node (ref "R25") (pin "2") (pinfunction "2_2") (pintype "passive"))
    )
    (net (code "143") (name "Net-(J1-TWC)") (class "Default")
      (node (ref "J1") (pin "37") (pinfunction "TWC_37") (pintype "passive"))
      (node (ref "R26") (pin "2") (pinfunction "2_2") (pintype "passive"))
    )
    (net (code "144") (name "Net-(J1-TWO)") (class "Default")
      (node (ref "J1") (pin "38") (pinfunction "TWO_38") (pintype "passive"))
      (node (ref "R27") (pin "2") (pinfunction "2_2") (pintype "passive"))
    )
    (net (code "145") (name "Net-(J1-VSYNC)") (class "Default")
      (node (ref "J1") (pin "41") (pinfunction "VSYNC_41") (pintype "passive"))
      (node (ref "R29") (pin "2") (pinfunction "2_2") (pintype "passive"))
    )
    (net (code "146") (name "Net-(SW1-OFF1)") (class "Default")
      (node (ref "R1") (pin "2") (pinfunction "2_2") (pintype "passive"))
      (node (ref "SW1") (pin "8") (pinfunction "OFF1_8") (pintype "passive"))
    )
    (net (code "147") (name "Net-(SW1-OFF2)") (class "Default")
      (node (ref "R2") (pin "2") (pinfunction "2_2") (pintype "passive"))
      (node (ref "SW1") (pin "7") (pinfunction "OFF2_7") (pintype "passive"))
    )
    (net (code "148") (name "Net-(SW1-OFF3)") (class "Default")
      (node (ref "R3") (pin "2") (pinfunction "2_2") (pintype "passive"))
      (node (ref "SW1") (pin "6") (pinfunction "OFF3_6") (pintype "passive"))
    )
    (net (code "149") (name "Net-(SW1-OFF4)") (class "Default")
      (node (ref "R4") (pin "2") (pinfunction "2_2") (pintype "passive"))
      (node (ref "SW1") (pin "5") (pinfunction "OFF4_5") (pintype "passive"))
    )
    (net (code "150") (name "Net-(SW1-ON1)") (class "Default")
      (node (ref "R36") (pin "1") (pinfunction "1_1") (pintype "passive"))
      (node (ref "R37") (pin "1") (pinfunction "1_1") (pintype "passive"))
      (node (ref "SW1") (pin "1") (pinfunction "ON1_1") (pintype "passive"))
    )
    (net (code "151") (name "Net-(SW1-ON2)") (class "Default")
      (node (ref "R38") (pin "1") (pinfunction "1_1") (pintype "passive"))
      (node (ref "R39") (pin "1") (pinfunction "1_1") (pintype "passive"))
      (node (ref "SW1") (pin "2") (pinfunction "ON2_2") (pintype "passive"))
    )
    (net (code "152") (name "USB_OTG1_VBUS") (class "Default")
      (node (ref "U1") (pin "25") (pinfunction "25_25") (pintype "passive"))
    )
    (net (code "153") (name "VDD_3V3") (class "Default")
      (node (ref "C2") (pin "1") (pinfunction "1_1") (pintype "passive"))
      (node (ref "J1") (pin "3") (pinfunction "3V3_3") (pintype "passive"))
      (node (ref "J1") (pin "4") (pinfunction "3V3_1_4") (pintype "passive"))
      (node (ref "U1") (pin "37") (pinfunction "37_37") (pintype "passive"))
      (node (ref "U1") (pin "38") (pinfunction "38_38") (pintype "passive"))
    )
    (net (code "154") (name "VDD_5V") (class "Default")
      (node (ref "C1") (pin "1") (pinfunction "1_1") (pintype "passive"))
      (node (ref "J1") (pin "1") (pinfunction "5V_1") (pintype "passive"))
      (node (ref "J1") (pin "2") (pinfunction "5V_1_2") (pintype "passive"))
      (node (ref "U1") (pin "24") (pinfunction "24_24") (pintype "passive"))
    )
    (net (code "155") (name "VDD_BAT") (class "Default")
      (node (ref "U1") (pin "39") (pinfunction "39_39") (pintype "passive"))
    )
    (net (code "156") (name "unconnected-(J1-B0-Pad7)") (class "Default")
      (node (ref "J1") (pin "7") (pinfunction "B0_7") (pintype "passive"))
    )
    (net (code "157") (name "unconnected-(J1-B1-Pad8)") (class "Default")
      (node (ref "J1") (pin "8") (pinfunction "B1_8") (pintype "passive"))
    )
    (net (code "158") (name "unconnected-(J1-B2-Pad9)") (class "Default")
      (node (ref "J1") (pin "9") (pinfunction "B2_9") (pintype "passive"))
    )
    (net (code "159") (name "unconnected-(J1-G0-Pad15)") (class "Default")
      (node (ref "J1") (pin "15") (pinfunction "G0_15") (pintype "passive"))
    )
    (net (code "160") (name "unconnected-(J1-G1-Pad16)") (class "Default")
      (node (ref "J1") (pin "16") (pinfunction "G1_16") (pintype "passive"))
    )
    (net (code "161") (name "unconnected-(J1-LR-Pad49)") (class "Default")
      (node (ref "J1") (pin "49") (pinfunction "LR_49") (pintype "passive"))
    )
    (net (code "162") (name "unconnected-(J1-R0-Pad23)") (class "Default")
      (node (ref "J1") (pin "23") (pinfunction "R0_23") (pintype "passive"))
    )
    (net (code "163") (name "unconnected-(J1-R1-Pad24)") (class "Default")
      (node (ref "J1") (pin "24") (pinfunction "R1_24") (pintype "passive"))
    )
    (net (code "164") (name "unconnected-(J1-R2-Pad25)") (class "Default")
      (node (ref "J1") (pin "25") (pinfunction "R2_25") (pintype "passive"))
    )
    (net (code "165") (name "unconnected-(U1-Pad33)") (class "Default")
      (node (ref "U1") (pin "33") (pinfunction "33_33") (pintype "passive"))
    )
    (net (code "166") (name "unconnected-(U1-Pad34)") (class "Default")
      (node (ref "U1") (pin "34") (pinfunction "34_34") (pintype "passive"))
    )
  )
)
